# SI7051_SMD_603.net
KiCad netlist of a schematic drawn in EAGLE
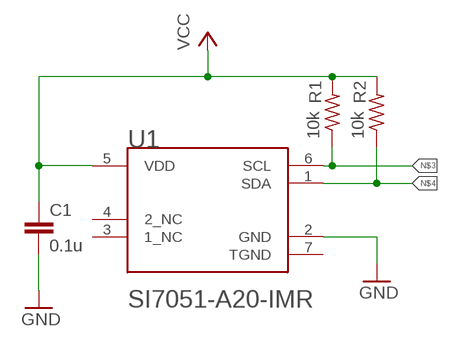
[diagram p0: schematic, sheet 1]

(export (version "E")
  (design (tool "Eeschema 10.0.6"))
  (components
    (comp (ref "C1")
      (value "0.1u")
      (footprint "eagle-import:C0603")
      (libsource (lib "eagle-import") (part "C-EUC0603"))
    )
    (comp (ref "R1")
      (value "10k")
      (footprint "eagle-import:R0603")
      (libsource (lib "eagle-import") (part "R-US_R0603"))
    )
    (comp (ref "R2")
      (value "10k")
      (footprint "eagle-import:R0603")
      (libsource (lib "eagle-import") (part "R-US_R0603"))
    )
    (comp (ref "U1")
      (value "SILICON_LABS_SI7051-A20-IMRSILICON_LABS_SI7051-A20-IMR_0_3")
      (footprint "eagle-import:SILICON_LABS_SI7051-A20-IMR_3")
      (fields
        (field (name "DIGIKEY_PART_NUMBER") "336-4764-1-ND")
        (field (name "MF") "Silicon Labs")
        (field (name "MOUSER_PART_NUMBER") "634-SI7051-A20-IMR")
      )
      (libsource (lib "eagle-import") (part "SILICON_LABS_SI7051-A20-IMRSILICON_LABS_SI7051-A20-IMR_0_3"))
    )
  )
  (nets
    (net (code "1") (name "/TGND") (class "Default")
      (node (ref "U1") (pin "7") (pinfunction "TGND_7") (pintype "power_in"))
    )
    (net (code "2") (name "GND") (class "Default")
      (node (ref "C1") (pin "2") (pinfunction "2_2") (pintype "passive"))
      (node (ref "U1") (pin "2") (pinfunction "GND_2") (pintype "power_in"))
    )
    (net (code "3") (name "N$3") (class "Default")
      (node (ref "R1") (pin "1") (pinfunction "1_1") (pintype "passive"))
      (node (ref "U1") (pin "6") (pinfunction "SCL_6") (pintype "input"))
    )
    (net (code "4") (name "N$4") (class "Default")
      (node (ref "R2") (pin "1") (pinfunction "1_1") (pintype "passive"))
      (node (ref "U1") (pin "1") (pinfunction "SDA_1") (pintype "bidirectional"))
    )
    (net (code "5") (name "VCC") (class "Default")
      (node (ref "C1") (pin "1") (pinfunction "1_1") (pintype "passive"))
      (node (ref "R1") (pin "2") (pinfunction "2_2") (pintype "passive"))
      (node (ref "R2") (pin "2") (pinfunction "2_2") (pintype "passive"))
      (node (ref "U1") (pin "5") (pinfunction "VDD_5") (pintype "power_in"))
    )
    (net (code "6") (name "unconnected-(U1-1_NC-Pad3)") (class "Default")
      (node (ref "U1") (pin "3") (pinfunction "1_NC_3") (pintype "passive"))
    )
    (net (code "7") (name "unconnected-(U1-2_NC-Pad4)") (class "Default")
      (node (ref "U1") (pin "4") (pinfunction "2_NC_4") (pintype "passive"))
    )
  )
)
